# ADC-RDC-FPGA.net
KiCad netlist of a schematic drawn in Altium Designer
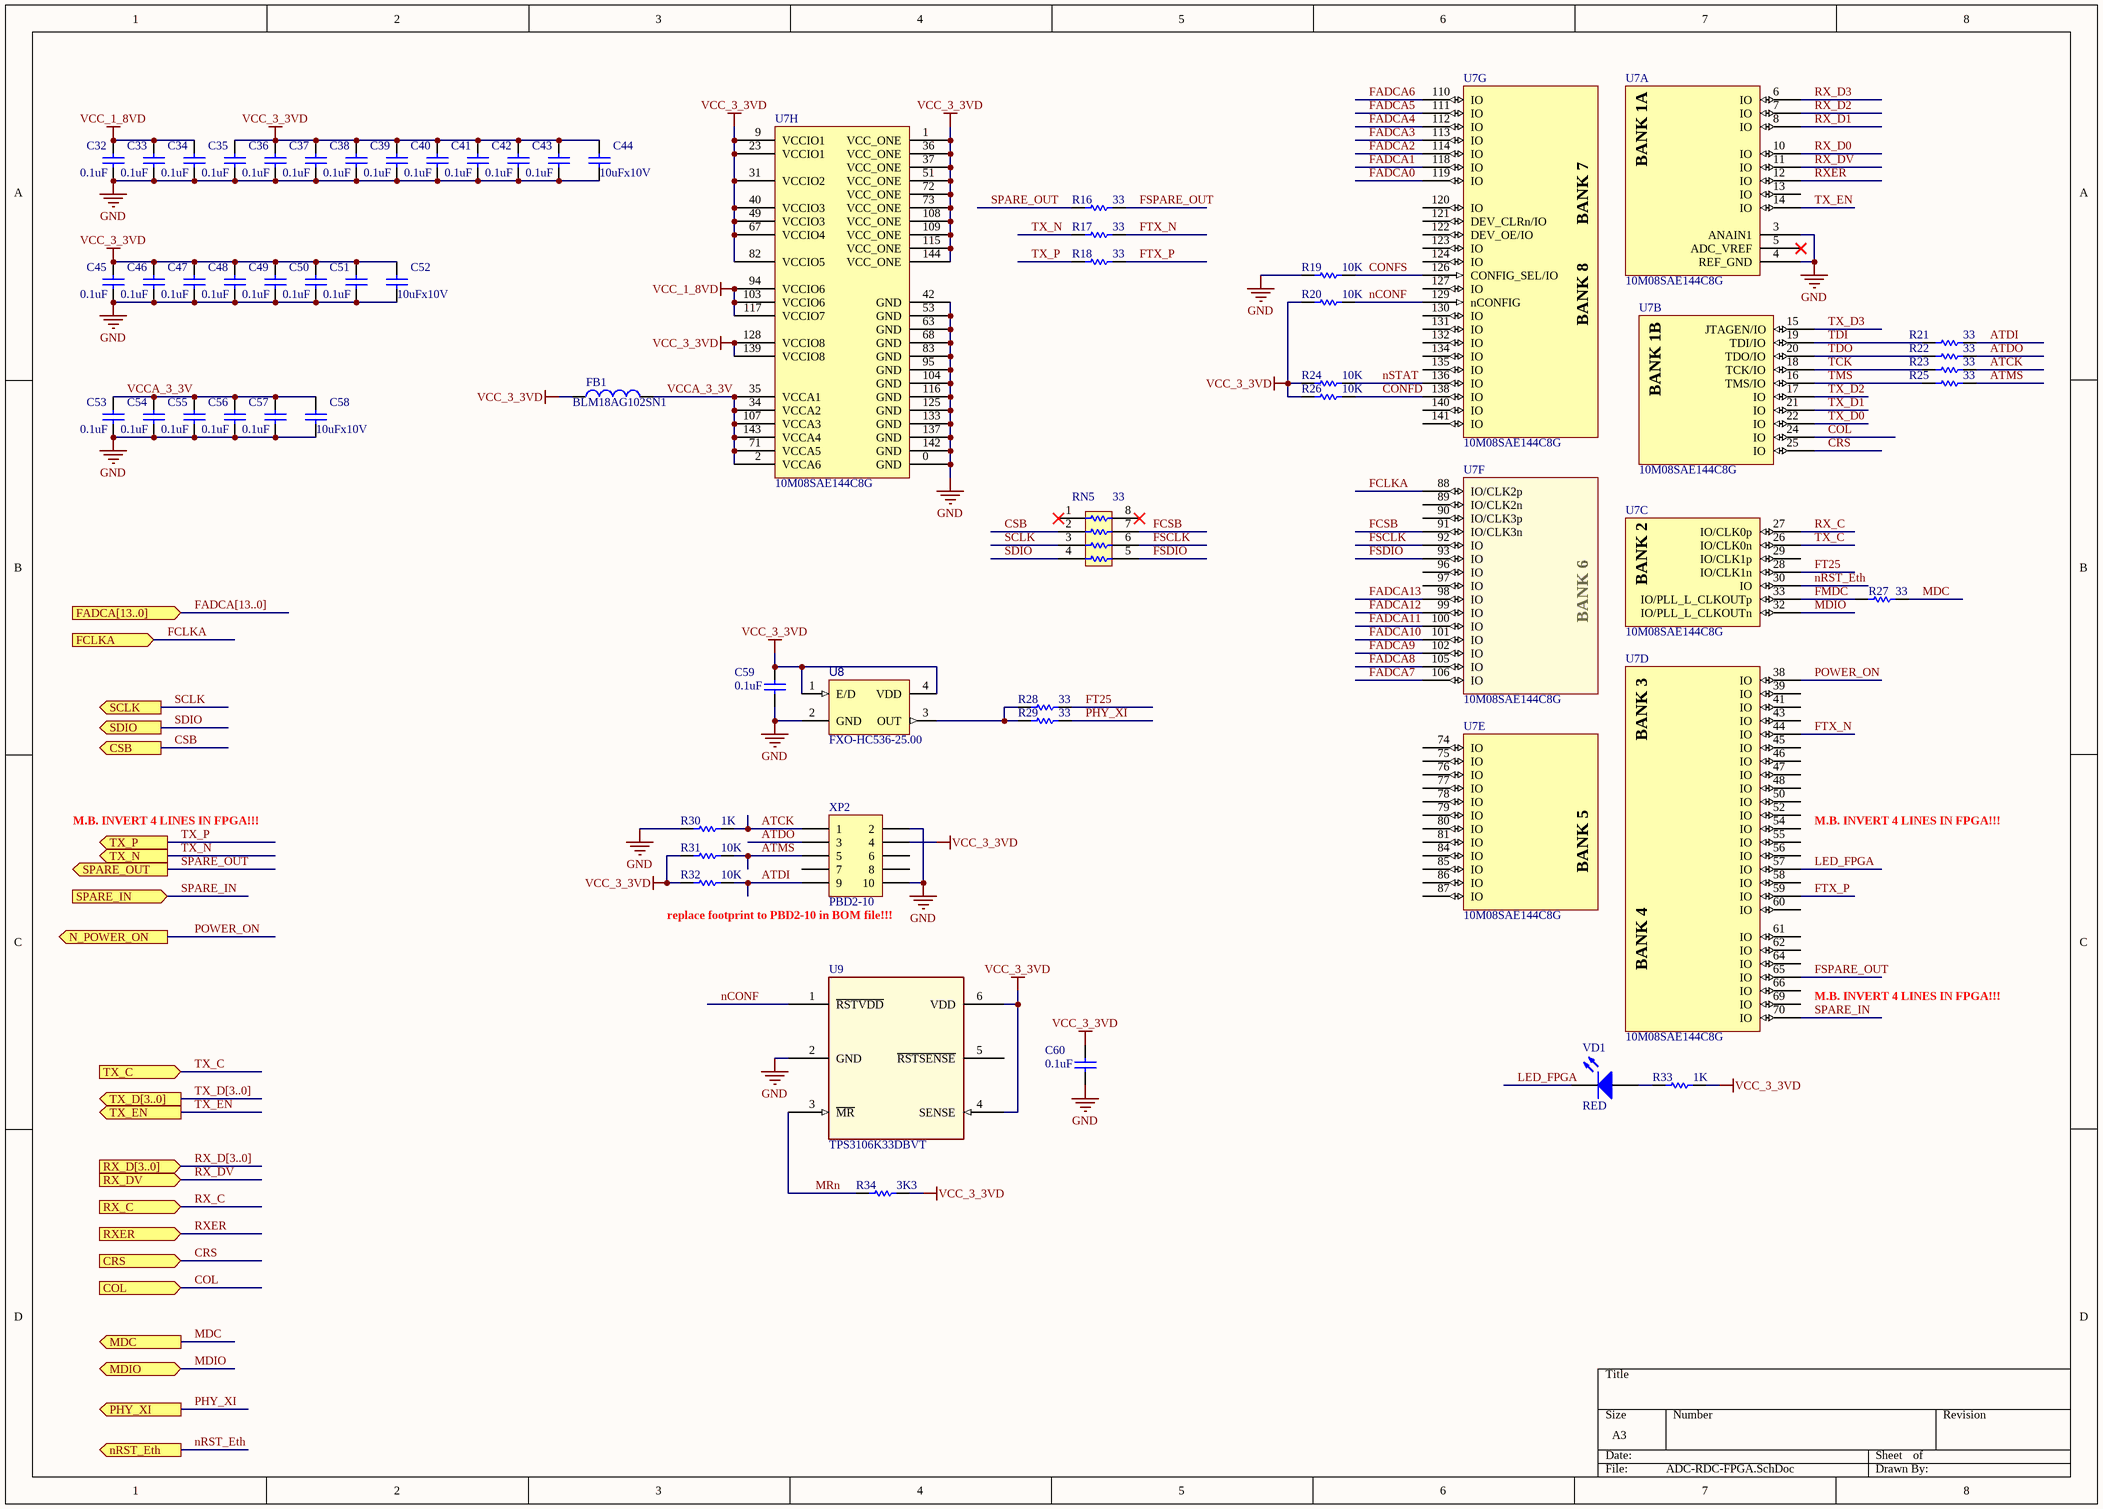
[diagram p0: ADC-RDC-FPGA.SchDoc]

(export (version "E")
  (design (tool "Eeschema 10.0.6"))
  (components
    (comp (ref "C32")
      (value "0.1uF")
      (footprint "C0603")
      (description "Capacitor, 2pin")
      (libsource (lib "GC500EM2") (part "Cap"))
    )
    (comp (ref "C33")
      (value "0.1uF")
      (footprint "C0603")
      (description "Capacitor, 2pin")
      (libsource (lib "GC500EM2") (part "Cap"))
    )
    (comp (ref "C34")
      (value "0.1uF")
      (footprint "C0603")
      (description "Capacitor, 2pin")
      (libsource (lib "GC500EM2") (part "Cap"))
    )
    (comp (ref "C35")
      (value "0.1uF")
      (footprint "C0603")
      (description "Capacitor, 2pin")
      (libsource (lib "GC500EM2") (part "Cap"))
    )
    (comp (ref "C36")
      (value "0.1uF")
      (footprint "C0603")
      (description "Capacitor, 2pin")
      (libsource (lib "GC500EM2") (part "Cap"))
    )
    (comp (ref "C37")
      (value "0.1uF")
      (footprint "C0603")
      (description "Capacitor, 2pin")
      (libsource (lib "GC500EM2") (part "Cap"))
    )
    (comp (ref "C38")
      (value "0.1uF")
      (footprint "C0603")
      (description "Capacitor, 2pin")
      (libsource (lib "GC500EM2") (part "Cap"))
    )
    (comp (ref "C39")
      (value "0.1uF")
      (footprint "C0603")
      (description "Capacitor, 2pin")
      (libsource (lib "GC500EM2") (part "Cap"))
    )
    (comp (ref "C40")
      (value "0.1uF")
      (footprint "C0603")
      (description "Capacitor, 2pin")
      (libsource (lib "GC500EM2") (part "Cap"))
    )
    (comp (ref "C41")
      (value "0.1uF")
      (footprint "C0603")
      (description "Capacitor, 2pin")
      (libsource (lib "GC500EM2") (part "Cap"))
    )
    (comp (ref "C42")
      (value "0.1uF")
      (footprint "C0603")
      (description "Capacitor, 2pin")
      (libsource (lib "GC500EM2") (part "Cap"))
    )
    (comp (ref "C43")
      (value "0.1uF")
      (footprint "C0603")
      (description "Capacitor, 2pin")
      (libsource (lib "GC500EM2") (part "Cap"))
    )
    (comp (ref "C44")
      (value "10uFx10V")
      (footprint "C0805")
      (description "Capacitor, 2pin")
      (libsource (lib "GC500EM2") (part "Cap"))
    )
    (comp (ref "C45")
      (value "0.1uF")
      (footprint "C0603")
      (description "Capacitor, 2pin")
      (libsource (lib "GC500EM2") (part "Cap"))
    )
    (comp (ref "C46")
      (value "0.1uF")
      (footprint "C0603")
      (description "Capacitor, 2pin")
      (libsource (lib "GC500EM2") (part "Cap"))
    )
    (comp (ref "C47")
      (value "0.1uF")
      (footprint "C0603")
      (description "Capacitor, 2pin")
      (libsource (lib "GC500EM2") (part "Cap"))
    )
    (comp (ref "C48")
      (value "0.1uF")
      (footprint "C0603")
      (description "Capacitor, 2pin")
      (libsource (lib "GC500EM2") (part "Cap"))
    )
    (comp (ref "C49")
      (value "0.1uF")
      (footprint "C0603")
      (description "Capacitor, 2pin")
      (libsource (lib "GC500EM2") (part "Cap"))
    )
    (comp (ref "C50")
      (value "0.1uF")
      (footprint "C0603")
      (description "Capacitor, 2pin")
      (libsource (lib "GC500EM2") (part "Cap"))
    )
    (comp (ref "C51")
      (value "0.1uF")
      (footprint "C0603")
      (description "Capacitor, 2pin")
      (libsource (lib "GC500EM2") (part "Cap"))
    )
    (comp (ref "C52")
      (value "10uFx10V")
      (footprint "C0805")
      (description "Capacitor, 2pin")
      (libsource (lib "GC500EM2") (part "Cap"))
    )
    (comp (ref "C53")
      (value "0.1uF")
      (footprint "C0603")
      (description "Capacitor, 2pin")
      (libsource (lib "GC500EM2") (part "Cap"))
    )
    (comp (ref "C54")
      (value "0.1uF")
      (footprint "C0603")
      (description "Capacitor, 2pin")
      (libsource (lib "GC500EM2") (part "Cap"))
    )
    (comp (ref "C55")
      (value "0.1uF")
      (footprint "C0603")
      (description "Capacitor, 2pin")
      (libsource (lib "GC500EM2") (part "Cap"))
    )
    (comp (ref "C56")
      (value "0.1uF")
      (footprint "C0603")
      (description "Capacitor, 2pin")
      (libsource (lib "GC500EM2") (part "Cap"))
    )
    (comp (ref "C57")
      (value "0.1uF")
      (footprint "C0603")
      (description "Capacitor, 2pin")
      (libsource (lib "GC500EM2") (part "Cap"))
    )
    (comp (ref "C58")
      (value "10uFx10V")
      (footprint "C0805")
      (description "Capacitor, 2pin")
      (libsource (lib "GC500EM2") (part "Cap"))
    )
    (comp (ref "C59")
      (value "0.1uF")
      (footprint "C0603")
      (description "Capacitor, 2pin")
      (libsource (lib "GC500EM2") (part "Cap"))
    )
    (comp (ref "C60")
      (value "0.1uF")
      (footprint "C0603")
      (description "Capacitor, 2pin")
      (libsource (lib "GC500EM2") (part "Cap"))
    )
    (comp (ref "FB1")
      (value "BLM18AG102SN1")
      (footprint "R0603")
      (description "Inductor, 2pin")
      (libsource (lib "GC500EM2") (part "Inductor"))
    )
    (comp (ref "R16")
      (value "33")
      (footprint "R0603")
      (description "Resistor, 2pin")
      (libsource (lib "GC500EM2") (part "RES"))
    )
    (comp (ref "R17")
      (value "33")
      (footprint "R0603")
      (description "Resistor, 2pin")
      (libsource (lib "GC500EM2") (part "RES"))
    )
    (comp (ref "R18")
      (value "33")
      (footprint "R0603")
      (description "Resistor, 2pin")
      (libsource (lib "GC500EM2") (part "RES"))
    )
    (comp (ref "R19")
      (value "10K")
      (footprint "R0603")
      (description "Resistor, 2pin")
      (libsource (lib "GC500EM2") (part "RES"))
    )
    (comp (ref "R20")
      (value "10K")
      (footprint "R0603")
      (description "Resistor, 2pin")
      (libsource (lib "GC500EM2") (part "RES"))
    )
    (comp (ref "R21")
      (value "33")
      (footprint "R0603")
      (description "Resistor, 2pin")
      (libsource (lib "GC500EM2") (part "RES"))
    )
    (comp (ref "R22")
      (value "33")
      (footprint "R0603")
      (description "Resistor, 2pin")
      (libsource (lib "GC500EM2") (part "RES"))
    )
    (comp (ref "R23")
      (value "33")
      (footprint "R0603")
      (description "Resistor, 2pin")
      (libsource (lib "GC500EM2") (part "RES"))
    )
    (comp (ref "R24")
      (value "10K")
      (footprint "R0603")
      (description "Resistor, 2pin")
      (libsource (lib "GC500EM2") (part "RES"))
    )
    (comp (ref "R25")
      (value "33")
      (footprint "R0603")
      (description "Resistor, 2pin")
      (libsource (lib "GC500EM2") (part "RES"))
    )
    (comp (ref "R26")
      (value "10K")
      (footprint "R0603")
      (description "Resistor, 2pin")
      (libsource (lib "GC500EM2") (part "RES"))
    )
    (comp (ref "R27")
      (value "33")
      (footprint "R0603")
      (description "Resistor, 2pin")
      (libsource (lib "GC500EM2") (part "RES"))
    )
    (comp (ref "R28")
      (value "33")
      (footprint "R0603")
      (description "Resistor, 2pin")
      (libsource (lib "GC500EM2") (part "RES"))
    )
    (comp (ref "R29")
      (value "33")
      (footprint "R0603")
      (description "Resistor, 2pin")
      (libsource (lib "GC500EM2") (part "RES"))
    )
    (comp (ref "R30")
      (value "1K")
      (footprint "R0603")
      (description "Resistor, 2pin")
      (libsource (lib "GC500EM2") (part "RES"))
    )
    (comp (ref "R31")
      (value "10K")
      (footprint "R0603")
      (description "Resistor, 2pin")
      (libsource (lib "GC500EM2") (part "RES"))
    )
    (comp (ref "R32")
      (value "10K")
      (footprint "R0603")
      (description "Resistor, 2pin")
      (libsource (lib "GC500EM2") (part "RES"))
    )
    (comp (ref "R33")
      (value "1K")
      (footprint "R0603")
      (description "Resistor, 2pin")
      (libsource (lib "GC500EM2") (part "RES"))
    )
    (comp (ref "R34")
      (value "3K3")
      (footprint "R0603")
      (description "Resistor, 2pin")
      (libsource (lib "GC500EM2") (part "RES"))
    )
    (comp (ref "RN5")
      (value "33")
      (footprint "EXB38V")
      (description "x4 Resistor Array")
      (libsource (lib "GC500EM2") (part "x4 Resistor Array"))
    )
    (comp (ref "U7")
      (value "10M08SAE144C8G")
      (footprint "EQFP144_L")
      (libsource (lib "") (part "10M04SAE144C8G_2"))
    )
    (comp (ref "U8")
      (value "FXO-HC536-25.00")
      (footprint "HC5")
      (description "Surface Mount Crystal Oscillator")
      (libsource (lib "GC500EM2") (part "SG-636PTF-40.0000"))
    )
    (comp (ref "U9")
      (value "TPS3106K33DBVT")
      (footprint "SOT23-6")
      (libsource (lib "GC500EM2") (part "TPS3106"))
    )
    (comp (ref "VD1")
      (value "RED")
      (footprint "D0805")
      (description "Typical GaAs LED")
      (libsource (lib "GC500EM2") (part "LED"))
    )
    (comp (ref "XP2")
      (value "PBD2-10")
      (footprint "PLD2-10")
      (description "Header, 5-Pin, Dual row")
      (libsource (lib "GC500EM2") (part "Header 5X2"))
    )
  )
  (nets
    (net (code "1") (name "/ATCK") (class "Default")
      (node (ref "R23") (pin "2") (pinfunction "2_2") (pintype "passive"))
      (node (ref "R30") (pin "2") (pinfunction "2_2") (pintype "passive"))
      (node (ref "XP2") (pin "1") (pinfunction "1_1") (pintype "passive"))
    )
    (net (code "2") (name "/ATDI") (class "Default")
      (node (ref "R21") (pin "2") (pinfunction "2_2") (pintype "passive"))
      (node (ref "R32") (pin "2") (pinfunction "2_2") (pintype "passive"))
      (node (ref "XP2") (pin "9") (pinfunction "9_9") (pintype "passive"))
    )
    (net (code "3") (name "/ATDO") (class "Default")
      (node (ref "R22") (pin "2") (pinfunction "2_2") (pintype "passive"))
      (node (ref "XP2") (pin "3") (pinfunction "3_3") (pintype "passive"))
    )
    (net (code "4") (name "/ATMS") (class "Default")
      (node (ref "R25") (pin "2") (pinfunction "2_2") (pintype "passive"))
      (node (ref "R31") (pin "2") (pinfunction "2_2") (pintype "passive"))
      (node (ref "XP2") (pin "5") (pinfunction "5_5") (pintype "passive"))
    )
    (net (code "5") (name "/COL") (class "Default")
      (node (ref "U7") (pin "24") (pinfunction "IO_24") (pintype "bidirectional"))
    )
    (net (code "6") (name "/CONFD") (class "Default")
      (node (ref "R26") (pin "2") (pinfunction "2_2") (pintype "passive"))
      (node (ref "U7") (pin "138") (pinfunction "IO_138") (pintype "bidirectional"))
    )
    (net (code "7") (name "/CONFS") (class "Default")
      (node (ref "R19") (pin "2") (pinfunction "2_2") (pintype "passive"))
      (node (ref "U7") (pin "126") (pinfunction "CONFIG_SEL/IO_126") (pintype "input"))
    )
    (net (code "8") (name "/CRS") (class "Default")
      (node (ref "U7") (pin "25") (pinfunction "IO_25") (pintype "bidirectional"))
    )
    (net (code "9") (name "/CSB") (class "Default") (node (ref "RN5") (pin "2") (pintype "passive")))
    (net (code "10") (name "/FADCA0") (class "Default")
      (node (ref "U7") (pin "119") (pinfunction "IO_119") (pintype "bidirectional"))
    )
    (net (code "11") (name "/FADCA1") (class "Default")
      (node (ref "U7") (pin "118") (pinfunction "IO_118") (pintype "bidirectional"))
    )
    (net (code "12") (name "/FADCA2") (class "Default")
      (node (ref "U7") (pin "114") (pinfunction "IO_114") (pintype "bidirectional"))
    )
    (net (code "13") (name "/FADCA3") (class "Default")
      (node (ref "U7") (pin "113") (pinfunction "IO_113") (pintype "bidirectional"))
    )
    (net (code "14") (name "/FADCA4") (class "Default")
      (node (ref "U7") (pin "112") (pinfunction "IO_112") (pintype "bidirectional"))
    )
    (net (code "15") (name "/FADCA5") (class "Default")
      (node (ref "U7") (pin "111") (pinfunction "IO_111") (pintype "bidirectional"))
    )
    (net (code "16") (name "/FADCA6") (class "Default")
      (node (ref "U7") (pin "110") (pinfunction "IO_110") (pintype "bidirectional"))
    )
    (net (code "17") (name "/FADCA7") (class "Default")
      (node (ref "U7") (pin "106") (pinfunction "IO_106") (pintype "bidirectional"))
    )
    (net (code "18") (name "/FADCA8") (class "Default")
      (node (ref "U7") (pin "105") (pinfunction "IO_105") (pintype "bidirectional"))
    )
    (net (code "19") (name "/FADCA9") (class "Default")
      (node (ref "U7") (pin "102") (pinfunction "IO_102") (pintype "bidirectional"))
    )
    (net (code "20") (name "/FADCA10") (class "Default")
      (node (ref "U7") (pin "101") (pinfunction "IO_101") (pintype "bidirectional"))
    )
    (net (code "21") (name "/FADCA11") (class "Default")
      (node (ref "U7") (pin "100") (pinfunction "IO_100") (pintype "bidirectional"))
    )
    (net (code "22") (name "/FADCA12") (class "Default")
      (node (ref "U7") (pin "99") (pinfunction "IO_99") (pintype "bidirectional"))
    )
    (net (code "23") (name "/FADCA13") (class "Default")
      (node (ref "U7") (pin "98") (pinfunction "IO_98") (pintype "bidirectional"))
    )
    (net (code "25") (name "/FCLKA") (class "Default")
      (node (ref "U7") (pin "88") (pinfunction "IO/CLK2p_88") (pintype "bidirectional"))
    )
    (net (code "26") (name "/FCSB") (class "Default")
      (node (ref "RN5") (pin "7") (pintype "passive"))
      (node (ref "U7") (pin "91") (pinfunction "IO/CLK3n_91") (pintype "bidirectional"))
    )
    (net (code "27") (name "/FMDC") (class "Default")
      (node (ref "R27") (pin "1") (pinfunction "1_1") (pintype "passive"))
      (node (ref "U7") (pin "33") (pinfunction "IO/PLL_L_CLKOUTp_33") (pintype "bidirectional"))
    )
    (net (code "28") (name "/FSCLK") (class "Default")
      (node (ref "RN5") (pin "6") (pintype "passive"))
      (node (ref "U7") (pin "92") (pinfunction "IO_92") (pintype "bidirectional"))
    )
    (net (code "29") (name "/FSDIO") (class "Default")
      (node (ref "RN5") (pin "5") (pintype "passive"))
      (node (ref "U7") (pin "93") (pinfunction "IO_93") (pintype "bidirectional"))
    )
    (net (code "30") (name "/FSPARE_OUT") (class "Default")
      (node (ref "R16") (pin "2") (pinfunction "2_2") (pintype "passive"))
      (node (ref "U7") (pin "65") (pinfunction "IO_65") (pintype "bidirectional"))
    )
    (net (code "31") (name "/FT25") (class "Default")
      (node (ref "R28") (pin "2") (pinfunction "2_2") (pintype "passive"))
      (node (ref "U7") (pin "28") (pinfunction "IO/CLK1n_28") (pintype "bidirectional"))
    )
    (net (code "32") (name "/FTX_N") (class "Default")
      (node (ref "R17") (pin "2") (pinfunction "2_2") (pintype "passive"))
      (node (ref "U7") (pin "44") (pinfunction "IO_44") (pintype "bidirectional"))
    )
    (net (code "33") (name "/FTX_P") (class "Default")
      (node (ref "R18") (pin "2") (pinfunction "2_2") (pintype "passive"))
      (node (ref "U7") (pin "59") (pinfunction "IO_59") (pintype "bidirectional"))
    )
    (net (code "34") (name "/LED_FPGA") (class "Default")
      (node (ref "U7") (pin "57") (pinfunction "IO_57") (pintype "bidirectional"))
      (node (ref "VD1") (pin "2") (pinfunction "K_2") (pintype "passive"))
    )
    (net (code "35") (name "/MDC") (class "Default")
      (node (ref "R27") (pin "2") (pinfunction "2_2") (pintype "passive"))
    )
    (net (code "36") (name "/MDIO") (class "Default")
      (node (ref "U7") (pin "32") (pinfunction "IO/PLL_L_CLKOUTn_32") (pintype "bidirectional"))
    )
    (net (code "37") (name "/MRn") (class "Default")
      (node (ref "R34") (pin "1") (pinfunction "1_1") (pintype "passive"))
      (node (ref "U9") (pin "3") (pinfunction "~{MR}_3") (pintype "input"))
    )
    (net (code "38") (name "/PHY_XI") (class "Default")
      (node (ref "R29") (pin "2") (pinfunction "2_2") (pintype "passive"))
    )
    (net (code "39") (name "/POWER_ON") (class "Default")
      (node (ref "U7") (pin "38") (pinfunction "IO_38") (pintype "bidirectional"))
    )
    (net (code "40") (name "/RXER") (class "Default")
      (node (ref "U7") (pin "12") (pinfunction "IO_12") (pintype "bidirectional"))
    )
    (net (code "41") (name "/RX_C") (class "Default")
      (node (ref "U7") (pin "27") (pinfunction "IO/CLK0p_27") (pintype "bidirectional"))
    )
    (net (code "42") (name "/RX_D0") (class "Default")
      (node (ref "U7") (pin "10") (pinfunction "IO_10") (pintype "bidirectional"))
    )
    (net (code "43") (name "/RX_D1") (class "Default")
      (node (ref "U7") (pin "8") (pinfunction "IO_8") (pintype "bidirectional"))
    )
    (net (code "44") (name "/RX_D2") (class "Default")
      (node (ref "U7") (pin "7") (pinfunction "IO_7") (pintype "bidirectional"))
    )
    (net (code "45") (name "/RX_D3") (class "Default")
      (node (ref "U7") (pin "6") (pinfunction "IO_6") (pintype "bidirectional"))
    )
    (net (code "46") (name "/RX_DV") (class "Default")
      (node (ref "U7") (pin "11") (pinfunction "IO_11") (pintype "bidirectional"))
    )
    (net (code "48") (name "/SCLK") (class "Default") (node (ref "RN5") (pin "3") (pintype "passive")))
    (net (code "49") (name "/SDIO") (class "Default") (node (ref "RN5") (pin "4") (pintype "passive")))
    (net (code "50") (name "/SPARE_IN") (class "Default")
      (node (ref "U7") (pin "70") (pinfunction "IO_70") (pintype "bidirectional"))
    )
    (net (code "51") (name "/SPARE_OUT") (class "Default")
      (node (ref "R16") (pin "1") (pinfunction "1_1") (pintype "passive"))
    )
    (net (code "52") (name "/TCK") (class "Default")
      (node (ref "R23") (pin "1") (pinfunction "1_1") (pintype "passive"))
      (node (ref "U7") (pin "18") (pinfunction "TCK/IO_18") (pintype "bidirectional"))
    )
    (net (code "53") (name "/TDI") (class "Default")
      (node (ref "R21") (pin "1") (pinfunction "1_1") (pintype "passive"))
      (node (ref "U7") (pin "19") (pinfunction "TDI/IO_19") (pintype "bidirectional"))
    )
    (net (code "54") (name "/TDO") (class "Default")
      (node (ref "R22") (pin "1") (pinfunction "1_1") (pintype "passive"))
      (node (ref "U7") (pin "20") (pinfunction "TDO/IO_20") (pintype "bidirectional"))
    )
    (net (code "55") (name "/TMS") (class "Default")
      (node (ref "R25") (pin "1") (pinfunction "1_1") (pintype "passive"))
      (node (ref "U7") (pin "16") (pinfunction "TMS/IO_16") (pintype "bidirectional"))
    )
    (net (code "56") (name "/TX_C") (class "Default")
      (node (ref "U7") (pin "26") (pinfunction "IO/CLK0n_26") (pintype "bidirectional"))
    )
    (net (code "57") (name "/TX_D0") (class "Default")
      (node (ref "U7") (pin "22") (pinfunction "IO_22") (pintype "bidirectional"))
    )
    (net (code "58") (name "/TX_D1") (class "Default")
      (node (ref "U7") (pin "21") (pinfunction "IO_21") (pintype "bidirectional"))
    )
    (net (code "59") (name "/TX_D2") (class "Default")
      (node (ref "U7") (pin "17") (pinfunction "IO_17") (pintype "bidirectional"))
    )
    (net (code "60") (name "/TX_D3") (class "Default")
      (node (ref "U7") (pin "15") (pinfunction "JTAGEN/IO_15") (pintype "bidirectional"))
    )
    (net (code "62") (name "/TX_EN") (class "Default")
      (node (ref "U7") (pin "14") (pinfunction "IO_14") (pintype "bidirectional"))
    )
    (net (code "63") (name "/TX_N") (class "Default")
      (node (ref "R17") (pin "1") (pinfunction "1_1") (pintype "passive"))
    )
    (net (code "64") (name "/TX_P") (class "Default")
      (node (ref "R18") (pin "1") (pinfunction "1_1") (pintype "passive"))
    )
    (net (code "65") (name "/VCCA_3_3V") (class "Default")
      (node (ref "C53") (pin "2") (pinfunction "2_2") (pintype "passive"))
      (node (ref "C54") (pin "2") (pinfunction "2_2") (pintype "passive"))
      (node (ref "C55") (pin "2") (pinfunction "2_2") (pintype "passive"))
      (node (ref "C56") (pin "2") (pinfunction "2_2") (pintype "passive"))
      (node (ref "C57") (pin "2") (pinfunction "2_2") (pintype "passive"))
      (node (ref "C58") (pin "1") (pinfunction "1_1") (pintype "passive"))
      (node (ref "FB1") (pin "1") (pinfunction "1_1") (pintype "passive"))
      (node (ref "U7") (pin "107") (pinfunction "VCCA3_107") (pintype "power_in"))
      (node (ref "U7") (pin "143") (pinfunction "VCCA4_143") (pintype "power_in"))
      (node (ref "U7") (pin "2") (pinfunction "VCCA6_2") (pintype "power_in"))
      (node (ref "U7") (pin "34") (pinfunction "VCCA2_34") (pintype "power_in"))
      (node (ref "U7") (pin "35") (pinfunction "VCCA1_35") (pintype "power_in"))
      (node (ref "U7") (pin "71") (pinfunction "VCCA5_71") (pintype "power_in"))
    )
    (net (code "66") (name "/nCONF") (class "Default")
      (node (ref "R20") (pin "2") (pinfunction "2_2") (pintype "passive"))
      (node (ref "U7") (pin "129") (pinfunction "nCONFIG_129") (pintype "input"))
      (node (ref "U9") (pin "1") (pinfunction "~{RSTVDD}_1") (pintype "open_collector"))
    )
    (net (code "67") (name "/nRST_Eth") (class "Default")
      (node (ref "U7") (pin "30") (pinfunction "IO_30") (pintype "bidirectional"))
    )
    (net (code "68") (name "/nSTAT") (class "Default")
      (node (ref "R24") (pin "2") (pinfunction "2_2") (pintype "passive"))
      (node (ref "U7") (pin "136") (pinfunction "IO_136") (pintype "bidirectional"))
    )
    (net (code "69") (name "GND") (class "Default")
      (node (ref "C32") (pin "1") (pinfunction "1_1") (pintype "passive"))
      (node (ref "C33") (pin "1") (pinfunction "1_1") (pintype "passive"))
      (node (ref "C34") (pin "1") (pinfunction "1_1") (pintype "passive"))
      (node (ref "C35") (pin "1") (pinfunction "1_1") (pintype "passive"))
      (node (ref "C36") (pin "1") (pinfunction "1_1") (pintype "passive"))
      (node (ref "C37") (pin "1") (pinfunction "1_1") (pintype "passive"))
      (node (ref "C38") (pin "1") (pinfunction "1_1") (pintype "passive"))
      (node (ref "C39") (pin "1") (pinfunction "1_1") (pintype "passive"))
      (node (ref "C40") (pin "1") (pinfunction "1_1") (pintype "passive"))
      (node (ref "C41") (pin "1") (pinfunction "1_1") (pintype "passive"))
      (node (ref "C42") (pin "1") (pinfunction "1_1") (pintype "passive"))
      (node (ref "C43") (pin "1") (pinfunction "1_1") (pintype "passive"))
      (node (ref "C44") (pin "2") (pinfunction "2_2") (pintype "passive"))
      (node (ref "C45") (pin "1") (pinfunction "1_1") (pintype "passive"))
      (node (ref "C46") (pin "1") (pinfunction "1_1") (pintype "passive"))
      (node (ref "C47") (pin "1") (pinfunction "1_1") (pintype "passive"))
      (node (ref "C48") (pin "1") (pinfunction "1_1") (pintype "passive"))
      (node (ref "C49") (pin "1") (pinfunction "1_1") (pintype "passive"))
      (node (ref "C50") (pin "1") (pinfunction "1_1") (pintype "passive"))
      (node (ref "C51") (pin "1") (pinfunction "1_1") (pintype "passive"))
      (node (ref "C52") (pin "2") (pinfunction "2_2") (pintype "passive"))
      (node (ref "C53") (pin "1") (pinfunction "1_1") (pintype "passive"))
      (node (ref "C54") (pin "1") (pinfunction "1_1") (pintype "passive"))
      (node (ref "C55") (pin "1") (pinfunction "1_1") (pintype "passive"))
      (node (ref "C56") (pin "1") (pinfunction "1_1") (pintype "passive"))
      (node (ref "C57") (pin "1") (pinfunction "1_1") (pintype "passive"))
      (node (ref "C58") (pin "2") (pinfunction "2_2") (pintype "passive"))
      (node (ref "C59") (pin "1") (pinfunction "1_1") (pintype "passive"))
      (node (ref "C60") (pin "1") (pinfunction "1_1") (pintype "passive"))
      (node (ref "R19") (pin "1") (pinfunction "1_1") (pintype "passive"))
      (node (ref "R30") (pin "1") (pinfunction "1_1") (pintype "passive"))
      (node (ref "U7") (pin "0") (pinfunction "GND_0") (pintype "power_in"))
      (node (ref "U7") (pin "104") (pinfunction "GND_104") (pintype "power_in"))
      (node (ref "U7") (pin "116") (pinfunction "GND_116") (pintype "power_in"))
      (node (ref "U7") (pin "125") (pinfunction "GND_125") (pintype "power_in"))
      (node (ref "U7") (pin "133") (pinfunction "GND_133") (pintype "power_in"))
      (node (ref "U7") (pin "137") (pinfunction "GND_137") (pintype "power_in"))
      (node (ref "U7") (pin "142") (pinfunction "GND_142") (pintype "power_in"))
      (node (ref "U7") (pin "3") (pinfunction "ANAIN1_3") (pintype "passive"))
      (node (ref "U7") (pin "4") (pinfunction "REF_GND_4") (pintype "passive"))
      (node (ref "U7") (pin "42") (pinfunction "GND_42") (pintype "power_in"))
      (node (ref "U7") (pin "53") (pinfunction "GND_53") (pintype "power_in"))
      (node (ref "U7") (pin "63") (pinfunction "GND_63") (pintype "power_in"))
      (node (ref "U7") (pin "68") (pinfunction "GND_68") (pintype "power_in"))
      (node (ref "U7") (pin "83") (pinfunction "GND_83") (pintype "power_in"))
      (node (ref "U7") (pin "95") (pinfunction "GND_95") (pintype "power_in"))
      (node (ref "U8") (pin "2") (pinfunction "GND_2") (pintype "power_in"))
      (node (ref "U9") (pin "2") (pinfunction "GND_2") (pintype "power_in"))
      (node (ref "XP2") (pin "10") (pinfunction "10_10") (pintype "passive"))
      (node (ref "XP2") (pin "2") (pinfunction "2_2") (pintype "passive"))
    )
    (net (code "70") (name "Net-(U8-OUT)") (class "Default")
      (node (ref "R28") (pin "1") (pinfunction "1_1") (pintype "passive"))
      (node (ref "R29") (pin "1") (pinfunction "1_1") (pintype "passive"))
      (node (ref "U8") (pin "3") (pinfunction "OUT_3") (pintype "output"))
    )
    (net (code "71") (name "Net-(VD1-A)") (class "Default")
      (node (ref "R33") (pin "2") (pinfunction "2_2") (pintype "passive"))
      (node (ref "VD1") (pin "1") (pinfunction "A_1") (pintype "passive"))
    )
    (net (code "72") (name "VCC_1_8VD") (class "Default")
      (node (ref "C32") (pin "2") (pinfunction "2_2") (pintype "passive"))
      (node (ref "C33") (pin "2") (pinfunction "2_2") (pintype "passive"))
      (node (ref "C34") (pin "2") (pinfunction "2_2") (pintype "passive"))
      (node (ref "U7") (pin "103") (pinfunction "VCCIO6_103") (pintype "power_in"))
      (node (ref "U7") (pin "117") (pinfunction "VCCIO7_117") (pintype "power_in"))
      (node (ref "U7") (pin "94") (pinfunction "VCCIO6_94") (pintype "power_in"))
    )
    (net (code "73") (name "VCC_3_3VD") (class "Default")
      (node (ref "C35") (pin "2") (pinfunction "2_2") (pintype "passive"))
      (node (ref "C36") (pin "2") (pinfunction "2_2") (pintype "passive"))
      (node (ref "C37") (pin "2") (pinfunction "2_2") (pintype "passive"))
      (node (ref "C38") (pin "2") (pinfunction "2_2") (pintype "passive"))
      (node (ref "C39") (pin "2") (pinfunction "2_2") (pintype "passive"))
      (node (ref "C40") (pin "2") (pinfunction "2_2") (pintype "passive"))
      (node (ref "C41") (pin "2") (pinfunction "2_2") (pintype "passive"))
      (node (ref "C42") (pin "2") (pinfunction "2_2") (pintype "passive"))
      (node (ref "C43") (pin "2") (pinfunction "2_2") (pintype "passive"))
      (node (ref "C44") (pin "1") (pinfunction "1_1") (pintype "passive"))
      (node (ref "C45") (pin "2") (pinfunction "2_2") (pintype "passive"))
      (node (ref "C46") (pin "2") (pinfunction "2_2") (pintype "passive"))
      (node (ref "C47") (pin "2") (pinfunction "2_2") (pintype "passive"))
      (node (ref "C48") (pin "2") (pinfunction "2_2") (pintype "passive"))
      (node (ref "C49") (pin "2") (pinfunction "2_2") (pintype "passive"))
      (node (ref "C50") (pin "2") (pinfunction "2_2") (pintype "passive"))
      (node (ref "C51") (pin "2") (pinfunction "2_2") (pintype "passive"))
      (node (ref "C52") (pin "1") (pinfunction "1_1") (pintype "passive"))
      (node (ref "C59") (pin "2") (pinfunction "2_2") (pintype "passive"))
      (node (ref "C60") (pin "2") (pinfunction "2_2") (pintype "passive"))
      (node (ref "FB1") (pin "2") (pinfunction "2_2") (pintype "passive"))
      (node (ref "R20") (pin "1") (pinfunction "1_1") (pintype "passive"))
      (node (ref "R24") (pin "1") (pinfunction "1_1") (pintype "passive"))
      (node (ref "R26") (pin "1") (pinfunction "1_1") (pintype "passive"))
      (node (ref "R31") (pin "1") (pinfunction "1_1") (pintype "passive"))
      (node (ref "R32") (pin "1") (pinfunction "1_1") (pintype "passive"))
      (node (ref "R33") (pin "1") (pinfunction "1_1") (pintype "passive"))
      (node (ref "R34") (pin "2") (pinfunction "2_2") (pintype "passive"))
      (node (ref "U7") (pin "1") (pinfunction "VCC_ONE_1") (pintype "power_in"))
      (node (ref "U7") (pin "108") (pinfunction "VCC_ONE_108") (pintype "power_in"))
      (node (ref "U7") (pin "109") (pinfunction "VCC_ONE_109") (pintype "power_in"))
      (node (ref "U7") (pin "115") (pinfunction "VCC_ONE_115") (pintype "power_in"))
      (node (ref "U7") (pin "128") (pinfunction "VCCIO8_128") (pintype "power_in"))
      (node (ref "U7") (pin "139") (pinfunction "VCCIO8_139") (pintype "power_in"))
      (node (ref "U7") (pin "144") (pinfunction "VCC_ONE_144") (pintype "power_in"))
      (node (ref "U7") (pin "23") (pinfunction "VCCIO1_23") (pintype "power_in"))
      (node (ref "U7") (pin "31") (pinfunction "VCCIO2_31") (pintype "power_in"))
      (node (ref "U7") (pin "36") (pinfunction "VCC_ONE_36") (pintype "power_in"))
      (node (ref "U7") (pin "37") (pinfunction "VCC_ONE_37") (pintype "power_in"))
      (node (ref "U7") (pin "40") (pinfunction "VCCIO3_40") (pintype "power_in"))
      (node (ref "U7") (pin "49") (pinfunction "VCCIO3_49") (pintype "power_in"))
      (node (ref "U7") (pin "51") (pinfunction "VCC_ONE_51") (pintype "power_in"))
      (node (ref "U7") (pin "67") (pinfunction "VCCIO4_67") (pintype "power_in"))
      (node (ref "U7") (pin "72") (pinfunction "VCC_ONE_72") (pintype "power_in"))
      (node (ref "U7") (pin "73") (pinfunction "VCC_ONE_73") (pintype "power_in"))
      (node (ref "U7") (pin "82") (pinfunction "VCCIO5_82") (pintype "power_in"))
      (node (ref "U7") (pin "9") (pinfunction "VCCIO1_9") (pintype "power_in"))
      (node (ref "U8") (pin "1") (pinfunction "E/D_1") (pintype "input"))
      (node (ref "U8") (pin "4") (pinfunction "VDD_4") (pintype "power_in"))
      (node (ref "U9") (pin "4") (pinfunction "SENSE_4") (pintype "input"))
      (node (ref "U9") (pin "6") (pinfunction "VDD_6") (pintype "power_in"))
      (node (ref "XP2") (pin "4") (pinfunction "4_4") (pintype "passive"))
    )
    (net (code "74") (name "unconnected-(RN5-Pad1)") (class "Default")
      (node (ref "RN5") (pin "1") (pintype "passive+no_connect"))
    )
    (net (code "75") (name "unconnected-(RN5-Pad8)") (class "Default")
      (node (ref "RN5") (pin "8") (pintype "passive+no_connect"))
    )
    (net (code "76") (name "unconnected-(U7A-ADC_VREF-Pad5)") (class "Default")
      (node (ref "U7") (pin "5") (pinfunction "ADC_VREF_5") (pintype "passive+no_connect"))
    )
    (net (code "77") (name "unconnected-(U7A-IO-Pad13)") (class "Default")
      (node (ref "U7") (pin "13") (pinfunction "IO_13") (pintype "bidirectional"))
    )
    (net (code "78") (name "unconnected-(U7C-IO{slash}CLK1p-Pad29)") (class "Default")
      (node (ref "U7") (pin "29") (pinfunction "IO/CLK1p_29") (pintype "bidirectional"))
    )
    (net (code "79") (name "unconnected-(U7D-IO-Pad39)") (class "Default")
      (node (ref "U7") (pin "39") (pinfunction "IO_39") (pintype "bidirectional"))
    )
    (net (code "80") (name "unconnected-(U7D-IO-Pad41)") (class "Default")
      (node (ref "U7") (pin "41") (pinfunction "IO_41") (pintype "bidirectional"))
    )
    (net (code "81") (name "unconnected-(U7D-IO-Pad43)") (class "Default")
      (node (ref "U7") (pin "43") (pinfunction "IO_43") (pintype "bidirectional"))
    )
    (net (code "82") (name "unconnected-(U7D-IO-Pad45)") (class "Default")
      (node (ref "U7") (pin "45") (pinfunction "IO_45") (pintype "bidirectional"))
    )
    (net (code "83") (name "unconnected-(U7D-IO-Pad46)") (class "Default")
      (node (ref "U7") (pin "46") (pinfunction "IO_46") (pintype "bidirectional"))
    )
    (net (code "84") (name "unconnected-(U7D-IO-Pad47)") (class "Default")
      (node (ref "U7") (pin "47") (pinfunction "IO_47") (pintype "bidirectional"))
    )
    (net (code "85") (name "unconnected-(U7D-IO-Pad48)") (class "Default")
      (node (ref "U7") (pin "48") (pinfunction "IO_48") (pintype "bidirectional"))
    )
    (net (code "86") (name "unconnected-(U7D-IO-Pad50)") (class "Default")
      (node (ref "U7") (pin "50") (pinfunction "IO_50") (pintype "bidirectional"))
    )
    (net (code "87") (name "unconnected-(U7D-IO-Pad52)") (class "Default")
      (node (ref "U7") (pin "52") (pinfunction "IO_52") (pintype "bidirectional"))
    )
    (net (code "88") (name "unconnected-(U7D-IO-Pad54)") (class "Default")
      (node (ref "U7") (pin "54") (pinfunction "IO_54") (pintype "bidirectional"))
    )
    (net (code "89") (name "unconnected-(U7D-IO-Pad55)") (class "Default")
      (node (ref "U7") (pin "55") (pinfunction "IO_55") (pintype "bidirectional"))
    )
    (net (code "90") (name "unconnected-(U7D-IO-Pad56)") (class "Default")
      (node (ref "U7") (pin "56") (pinfunction "IO_56") (pintype "bidirectional"))
    )
    (net (code "91") (name "unconnected-(U7D-IO-Pad58)") (class "Default")
      (node (ref "U7") (pin "58") (pinfunction "IO_58") (pintype "bidirectional"))
    )
    (net (code "92") (name "unconnected-(U7D-IO-Pad60)") (class "Default")
      (node (ref "U7") (pin "60") (pinfunction "IO_60") (pintype "bidirectional"))
    )
    (net (code "93") (name "unconnected-(U7D-IO-Pad61)") (class "Default")
      (node (ref "U7") (pin "61") (pinfunction "IO_61") (pintype "bidirectional"))
    )
    (net (code "94") (name "unconnected-(U7D-IO-Pad62)") (class "Default")
      (node (ref "U7") (pin "62") (pinfunction "IO_62") (pintype "bidirectional"))
    )
    (net (code "95") (name "unconnected-(U7D-IO-Pad64)") (class "Default")
      (node (ref "U7") (pin "64") (pinfunction "IO_64") (pintype "bidirectional"))
    )
    (net (code "96") (name "unconnected-(U7D-IO-Pad66)") (class "Default")
      (node (ref "U7") (pin "66") (pinfunction "IO_66") (pintype "bidirectional"))
    )
    (net (code "97") (name "unconnected-(U7D-IO-Pad69)") (class "Default")
      (node (ref "U7") (pin "69") (pinfunction "IO_69") (pintype "bidirectional"))
    )
    (net (code "98") (name "unconnected-(U7E-IO-Pad74)") (class "Default")
      (node (ref "U7") (pin "74") (pinfunction "IO_74") (pintype "bidirectional"))
    )
    (net (code "99") (name "unconnected-(U7E-IO-Pad75)") (class "Default")
      (node (ref "U7") (pin "75") (pinfunction "IO_75") (pintype "bidirectional"))
    )
    (net (code "100") (name "unconnected-(U7E-IO-Pad76)") (class "Default")
      (node (ref "U7") (pin "76") (pinfunction "IO_76") (pintype "bidirectional"))
    )
    (net (code "101") (name "unconnected-(U7E-IO-Pad77)") (class "Default")
      (node (ref "U7") (pin "77") (pinfunction "IO_77") (pintype "bidirectional"))
    )
    (net (code "102") (name "unconnected-(U7E-IO-Pad78)") (class "Default")
      (node (ref "U7") (pin "78") (pinfunction "IO_78") (pintype "bidirectional"))
    )
    (net (code "103") (name "unconnected-(U7E-IO-Pad79)") (class "Default")
      (node (ref "U7") (pin "79") (pinfunction "IO_79") (pintype "bidirectional"))
    )
    (net (code "104") (name "unconnected-(U7E-IO-Pad80)") (class "Default")
      (node (ref "U7") (pin "80") (pinfunction "IO_80") (pintype "bidirectional"))
    )
    (net (code "105") (name "unconnected-(U7E-IO-Pad81)") (class "Default")
      (node (ref "U7") (pin "81") (pinfunction "IO_81") (pintype "bidirectional"))
    )
    (net (code "106") (name "unconnected-(U7E-IO-Pad84)") (class "Default")
      (node (ref "U7") (pin "84") (pinfunction "IO_84") (pintype "bidirectional"))
    )
    (net (code "107") (name "unconnected-(U7E-IO-Pad85)") (class "Default")
      (node (ref "U7") (pin "85") (pinfunction "IO_85") (pintype "bidirectional"))
    )
    (net (code "108") (name "unconnected-(U7E-IO-Pad86)") (class "Default")
      (node (ref "U7") (pin "86") (pinfunction "IO_86") (pintype "bidirectional"))
    )
    (net (code "109") (name "unconnected-(U7E-IO-Pad87)") (class "Default")
      (node (ref "U7") (pin "87") (pinfunction "IO_87") (pintype "bidirectional"))
    )
    (net (code "110") (name "unconnected-(U7F-IO-Pad96)") (class "Default")
      (node (ref "U7") (pin "96") (pinfunction "IO_96") (pintype "bidirectional"))
    )
    (net (code "111") (name "unconnected-(U7F-IO-Pad97)") (class "Default")
      (node (ref "U7") (pin "97") (pinfunction "IO_97") (pintype "bidirectional"))
    )
    (net (code "112") (name "unconnected-(U7F-IO{slash}CLK2n-Pad89)") (class "Default")
      (node (ref "U7") (pin "89") (pinfunction "IO/CLK2n_89") (pintype "bidirectional"))
    )
    (net (code "113") (name "unconnected-(U7F-IO{slash}CLK3p-Pad90)") (class "Default")
      (node (ref "U7") (pin "90") (pinfunction "IO/CLK3p_90") (pintype "bidirectional"))
    )
    (net (code "114") (name "unconnected-(U7G-DEV_CLRn{slash}IO-Pad121)") (class "Default")
      (node (ref "U7") (pin "121") (pinfunction "DEV_CLRn/IO_121") (pintype "bidirectional"))
    )
    (net (code "115") (name "unconnected-(U7G-DEV_OE{slash}IO-Pad122)") (class "Default")
      (node (ref "U7") (pin "122") (pinfunction "DEV_OE/IO_122") (pintype "bidirectional"))
    )
    (net (code "116") (name "unconnected-(U7G-IO-Pad120)") (class "Default")
      (node (ref "U7") (pin "120") (pinfunction "IO_120") (pintype "bidirectional"))
    )
    (net (code "117") (name "unconnected-(U7G-IO-Pad123)") (class "Default")
      (node (ref "U7") (pin "123") (pinfunction "IO_123") (pintype "bidirectional"))
    )
    (net (code "118") (name "unconnected-(U7G-IO-Pad124)") (class "Default")
      (node (ref "U7") (pin "124") (pinfunction "IO_124") (pintype "bidirectional"))
    )
    (net (code "119") (name "unconnected-(U7G-IO-Pad127)") (class "Default")
      (node (ref "U7") (pin "127") (pinfunction "IO_127") (pintype "bidirectional"))
    )
    (net (code "120") (name "unconnected-(U7G-IO-Pad130)") (class "Default")
      (node (ref "U7") (pin "130") (pinfunction "IO_130") (pintype "bidirectional"))
    )
    (net (code "121") (name "unconnected-(U7G-IO-Pad131)") (class "Default")
      (node (ref "U7") (pin "131") (pinfunction "IO_131") (pintype "bidirectional"))
    )
    (net (code "122") (name "unconnected-(U7G-IO-Pad132)") (class "Default")
      (node (ref "U7") (pin "132") (pinfunction "IO_132") (pintype "bidirectional"))
    )
    (net (code "123") (name "unconnected-(U7G-IO-Pad134)") (class "Default")
      (node (ref "U7") (pin "134") (pinfunction "IO_134") (pintype "bidirectional"))
    )
    (net (code "124") (name "unconnected-(U7G-IO-Pad135)") (class "Default")
      (node (ref "U7") (pin "135") (pinfunction "IO_135") (pintype "bidirectional"))
    )
    (net (code "125") (name "unconnected-(U7G-IO-Pad140)") (class "Default")
      (node (ref "U7") (pin "140") (pinfunction "IO_140") (pintype "bidirectional"))
    )
    (net (code "126") (name "unconnected-(U7G-IO-Pad141)") (class "Default")
      (node (ref "U7") (pin "141") (pinfunction "IO_141") (pintype "bidirectional"))
    )
    (net (code "127") (name "unconnected-(U9-~{RSTSENSE}-Pad5)") (class "Default")
      (node (ref "U9") (pin "5") (pinfunction "~{RSTSENSE}_5") (pintype "open_collector"))
    )
    (net (code "128") (name "unconnected-(XP2-Pad6)") (class "Default")
      (node (ref "XP2") (pin "6") (pinfunction "6_6") (pintype "passive"))
    )
    (net (code "129") (name "unconnected-(XP2-Pad7)") (class "Default")
      (node (ref "XP2") (pin "7") (pinfunction "7_7") (pintype "passive"))
    )
    (net (code "130") (name "unconnected-(XP2-Pad8)") (class "Default")
      (node (ref "XP2") (pin "8") (pinfunction "8_8") (pintype "passive"))
    )
  )
)
